# RS232.net
KiCad netlist of a schematic drawn in Altium Designer
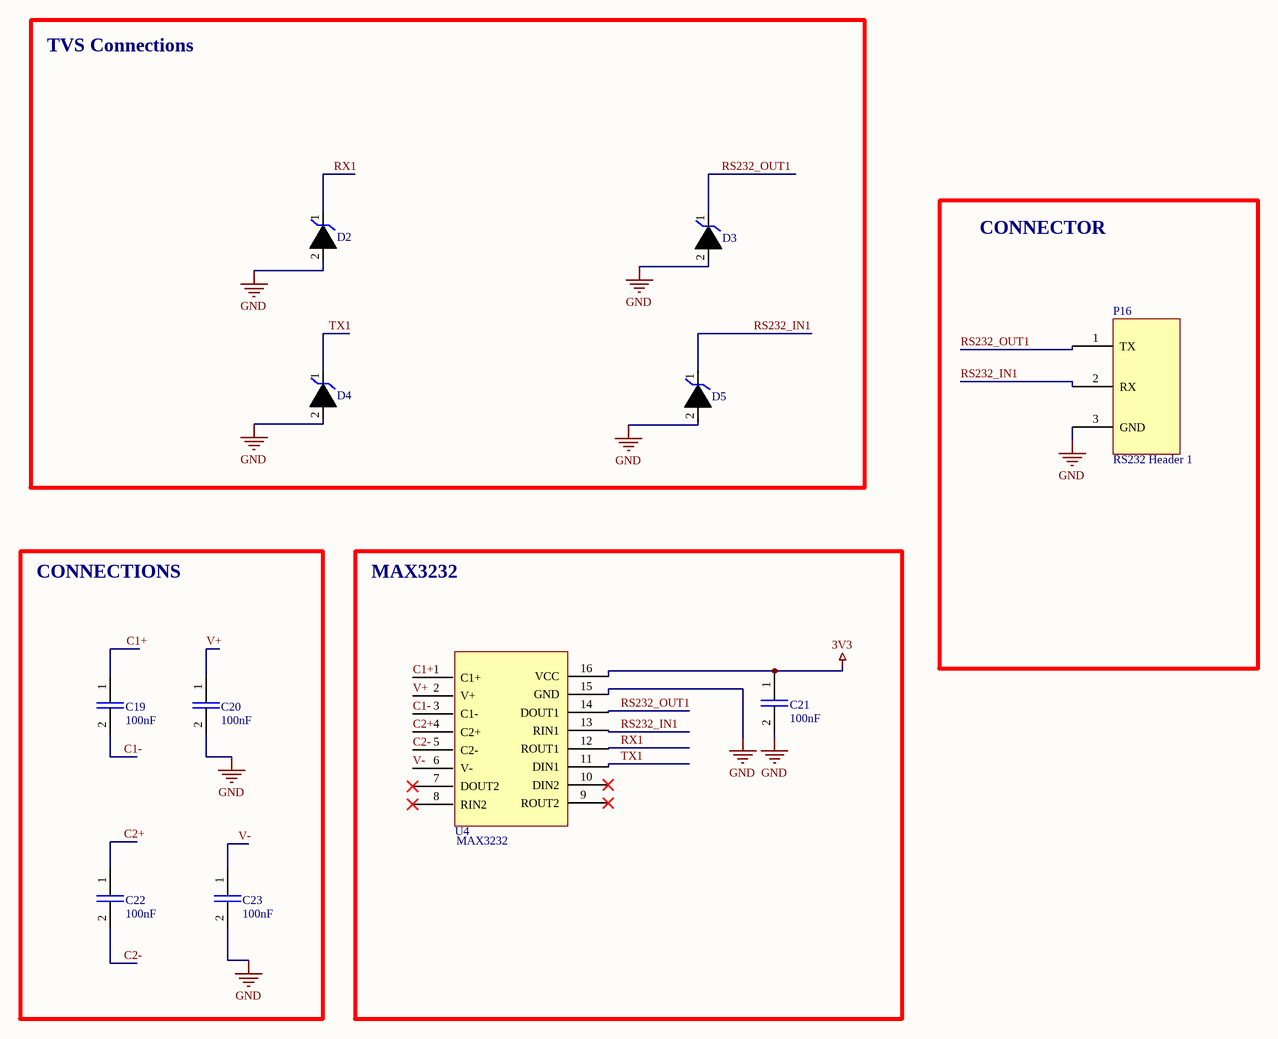
[diagram p0: RS232.SchDoc]

(export (version "E")
  (design (tool "Eeschema 10.0.6"))
  (components
    (comp (ref "C19")
      (value "100nF")
      (footprint "0603 Cap")
      (description "SMD 0603 (ceramic) capacitor")
      (fields
        (field (name "MANUFACTURER") "Murata")
        (field (name "MANUFACTURER PART NUMBER") "GRM21BR71C225KA12L")
      )
      (libsource (lib "Lib") (part "0603 Cap"))
    )
    (comp (ref "C20")
      (value "100nF")
      (footprint "0603 Cap")
      (description "SMD 0603 (ceramic) capacitor")
      (fields
        (field (name "MANUFACTURER") "Murata")
        (field (name "MANUFACTURER PART NUMBER") "GRM21BR71C225KA12L")
      )
      (libsource (lib "Lib") (part "0603 Cap"))
    )
    (comp (ref "C21")
      (value "100nF")
      (footprint "0603 Cap")
      (description "SMD 0603 (ceramic) capacitor")
      (fields
        (field (name "MANUFACTURER") "Murata")
        (field (name "MANUFACTURER PART NUMBER") "GRM21BR71C225KA12L")
      )
      (libsource (lib "Lib") (part "0603 Cap"))
    )
    (comp (ref "C22")
      (value "100nF")
      (footprint "0603 Cap")
      (description "SMD 0603 (ceramic) capacitor")
      (fields
        (field (name "MANUFACTURER") "Murata")
        (field (name "MANUFACTURER PART NUMBER") "GRM21BR71C225KA12L")
      )
      (libsource (lib "Lib") (part "0603 Cap"))
    )
    (comp (ref "C23")
      (value "100nF")
      (footprint "0603 Cap")
      (description "SMD 0603 (ceramic) capacitor")
      (fields
        (field (name "MANUFACTURER") "Murata")
        (field (name "MANUFACTURER PART NUMBER") "GRM21BR71C225KA12L")
      )
      (libsource (lib "Lib") (part "0603 Cap"))
    )
    (comp (ref "D2")
      (value "TVS")
      (footprint "TVS DIODE")
      (description "Schematic for TVS diode")
      (libsource (lib "Lib") (part "TVS Diode"))
    )
    (comp (ref "D3")
      (value "TVS")
      (footprint "TVS DIODE")
      (description "Schematic for TVS diode")
      (libsource (lib "Lib") (part "TVS Diode"))
    )
    (comp (ref "D4")
      (value "TVS")
      (footprint "TVS DIODE")
      (description "Schematic for TVS diode")
      (libsource (lib "Lib") (part "TVS Diode"))
    )
    (comp (ref "D5")
      (value "TVS")
      (footprint "TVS DIODE")
      (description "Schematic for TVS diode")
      (libsource (lib "Lib") (part "TVS Diode"))
    )
    (comp (ref "P16")
      (value "RS232 Header 1")
      (footprint "WR-TBL 322 3H")
      (description "322 Series 3 pin header")
      (libsource (lib "Lib") (part "322-3H"))
    )
    (comp (ref "U4")
      (value "MAX3232")
      (footprint "16-PIN SOIC")
      (description "16-Pin SOIC package IC schematic")
      (libsource (lib "Lib") (part "16-PIN SOIC"))
    )
  )
  (nets
    (net (code "1") (name "/C1+") (class "Default")
      (node (ref "C19") (pin "1") (pinfunction "11_1") (pintype "passive"))
      (node (ref "U4") (pin "1") (pinfunction "C1+_1") (pintype "passive"))
    )
    (net (code "2") (name "/C1-") (class "Default")
      (node (ref "C19") (pin "2") (pinfunction "12_2") (pintype "passive"))
      (node (ref "U4") (pin "3") (pinfunction "C1-_3") (pintype "passive"))
    )
    (net (code "3") (name "/C2+") (class "Default")
      (node (ref "C22") (pin "1") (pinfunction "11_1") (pintype "passive"))
      (node (ref "U4") (pin "4") (pinfunction "C2+_4") (pintype "passive"))
    )
    (net (code "4") (name "/C2-") (class "Default")
      (node (ref "C22") (pin "2") (pinfunction "12_2") (pintype "passive"))
      (node (ref "U4") (pin "5") (pinfunction "C2-_5") (pintype "passive"))
    )
    (net (code "5") (name "/RS232_IN1") (class "Default")
      (node (ref "D5") (pin "1") (pinfunction "1_1") (pintype "passive"))
      (node (ref "P16") (pin "2") (pinfunction "RX_2") (pintype "passive"))
      (node (ref "U4") (pin "13") (pinfunction "RIN1_13") (pintype "passive"))
    )
    (net (code "6") (name "/RS232_OUT1") (class "Default")
      (node (ref "D3") (pin "1") (pinfunction "1_1") (pintype "passive"))
      (node (ref "P16") (pin "1") (pinfunction "TX_1") (pintype "passive"))
      (node (ref "U4") (pin "14") (pinfunction "DOUT1_14") (pintype "passive"))
    )
    (net (code "7") (name "/RX1") (class "Default")
      (node (ref "D2") (pin "1") (pinfunction "1_1") (pintype "passive"))
      (node (ref "U4") (pin "12") (pinfunction "ROUT1_12") (pintype "passive"))
    )
    (net (code "8") (name "/TX1") (class "Default")
      (node (ref "D4") (pin "1") (pinfunction "1_1") (pintype "passive"))
      (node (ref "U4") (pin "11") (pinfunction "DIN1_11") (pintype "passive"))
    )
    (net (code "9") (name "/V+") (class "Default")
      (node (ref "C20") (pin "1") (pinfunction "11_1") (pintype "passive"))
      (node (ref "U4") (pin "2") (pinfunction "V+_2") (pintype "passive"))
    )
    (net (code "10") (name "/V-") (class "Default")
      (node (ref "C23") (pin "1") (pinfunction "11_1") (pintype "passive"))
      (node (ref "U4") (pin "6") (pinfunction "V-_6") (pintype "passive"))
    )
    (net (code "11") (name "3V3") (class "Default")
      (node (ref "C21") (pin "1") (pinfunction "11_1") (pintype "passive"))
      (node (ref "U4") (pin "16") (pinfunction "VCC_16") (pintype "passive"))
    )
    (net (code "12") (name "GND") (class "Default")
      (node (ref "C20") (pin "2") (pinfunction "12_2") (pintype "passive"))
      (node (ref "C21") (pin "2") (pinfunction "12_2") (pintype "passive"))
      (node (ref "C23") (pin "2") (pinfunction "12_2") (pintype "passive"))
      (node (ref "D2") (pin "2") (pinfunction "2_2") (pintype "passive"))
      (node (ref "D3") (pin "2") (pinfunction "2_2") (pintype "passive"))
      (node (ref "D4") (pin "2") (pinfunction "2_2") (pintype "passive"))
      (node (ref "D5") (pin "2") (pinfunction "2_2") (pintype "passive"))
      (node (ref "P16") (pin "3") (pinfunction "GND_3") (pintype "passive"))
      (node (ref "U4") (pin "15") (pinfunction "GND_15") (pintype "passive"))
    )
    (net (code "13") (name "unconnected-(U4-DIN2-Pad10)") (class "Default")
      (node (ref "U4") (pin "10") (pinfunction "DIN2_10") (pintype "passive+no_connect"))
    )
    (net (code "14") (name "unconnected-(U4-DOUT2-Pad7)") (class "Default")
      (node (ref "U4") (pin "7") (pinfunction "DOUT2_7") (pintype "passive+no_connect"))
    )
    (net (code "15") (name "unconnected-(U4-RIN2-Pad8)") (class "Default")
      (node (ref "U4") (pin "8") (pinfunction "RIN2_8") (pintype "passive+no_connect"))
    )
    (net (code "16") (name "unconnected-(U4-ROUT2-Pad9)") (class "Default")
      (node (ref "U4") (pin "9") (pinfunction "ROUT2_9") (pintype "passive+no_connect"))
    )
  )
)
